# SCH_LedGridWallHatV4_2026-08-28.net
KiCad netlist of a schematic drawn in EasyEDA
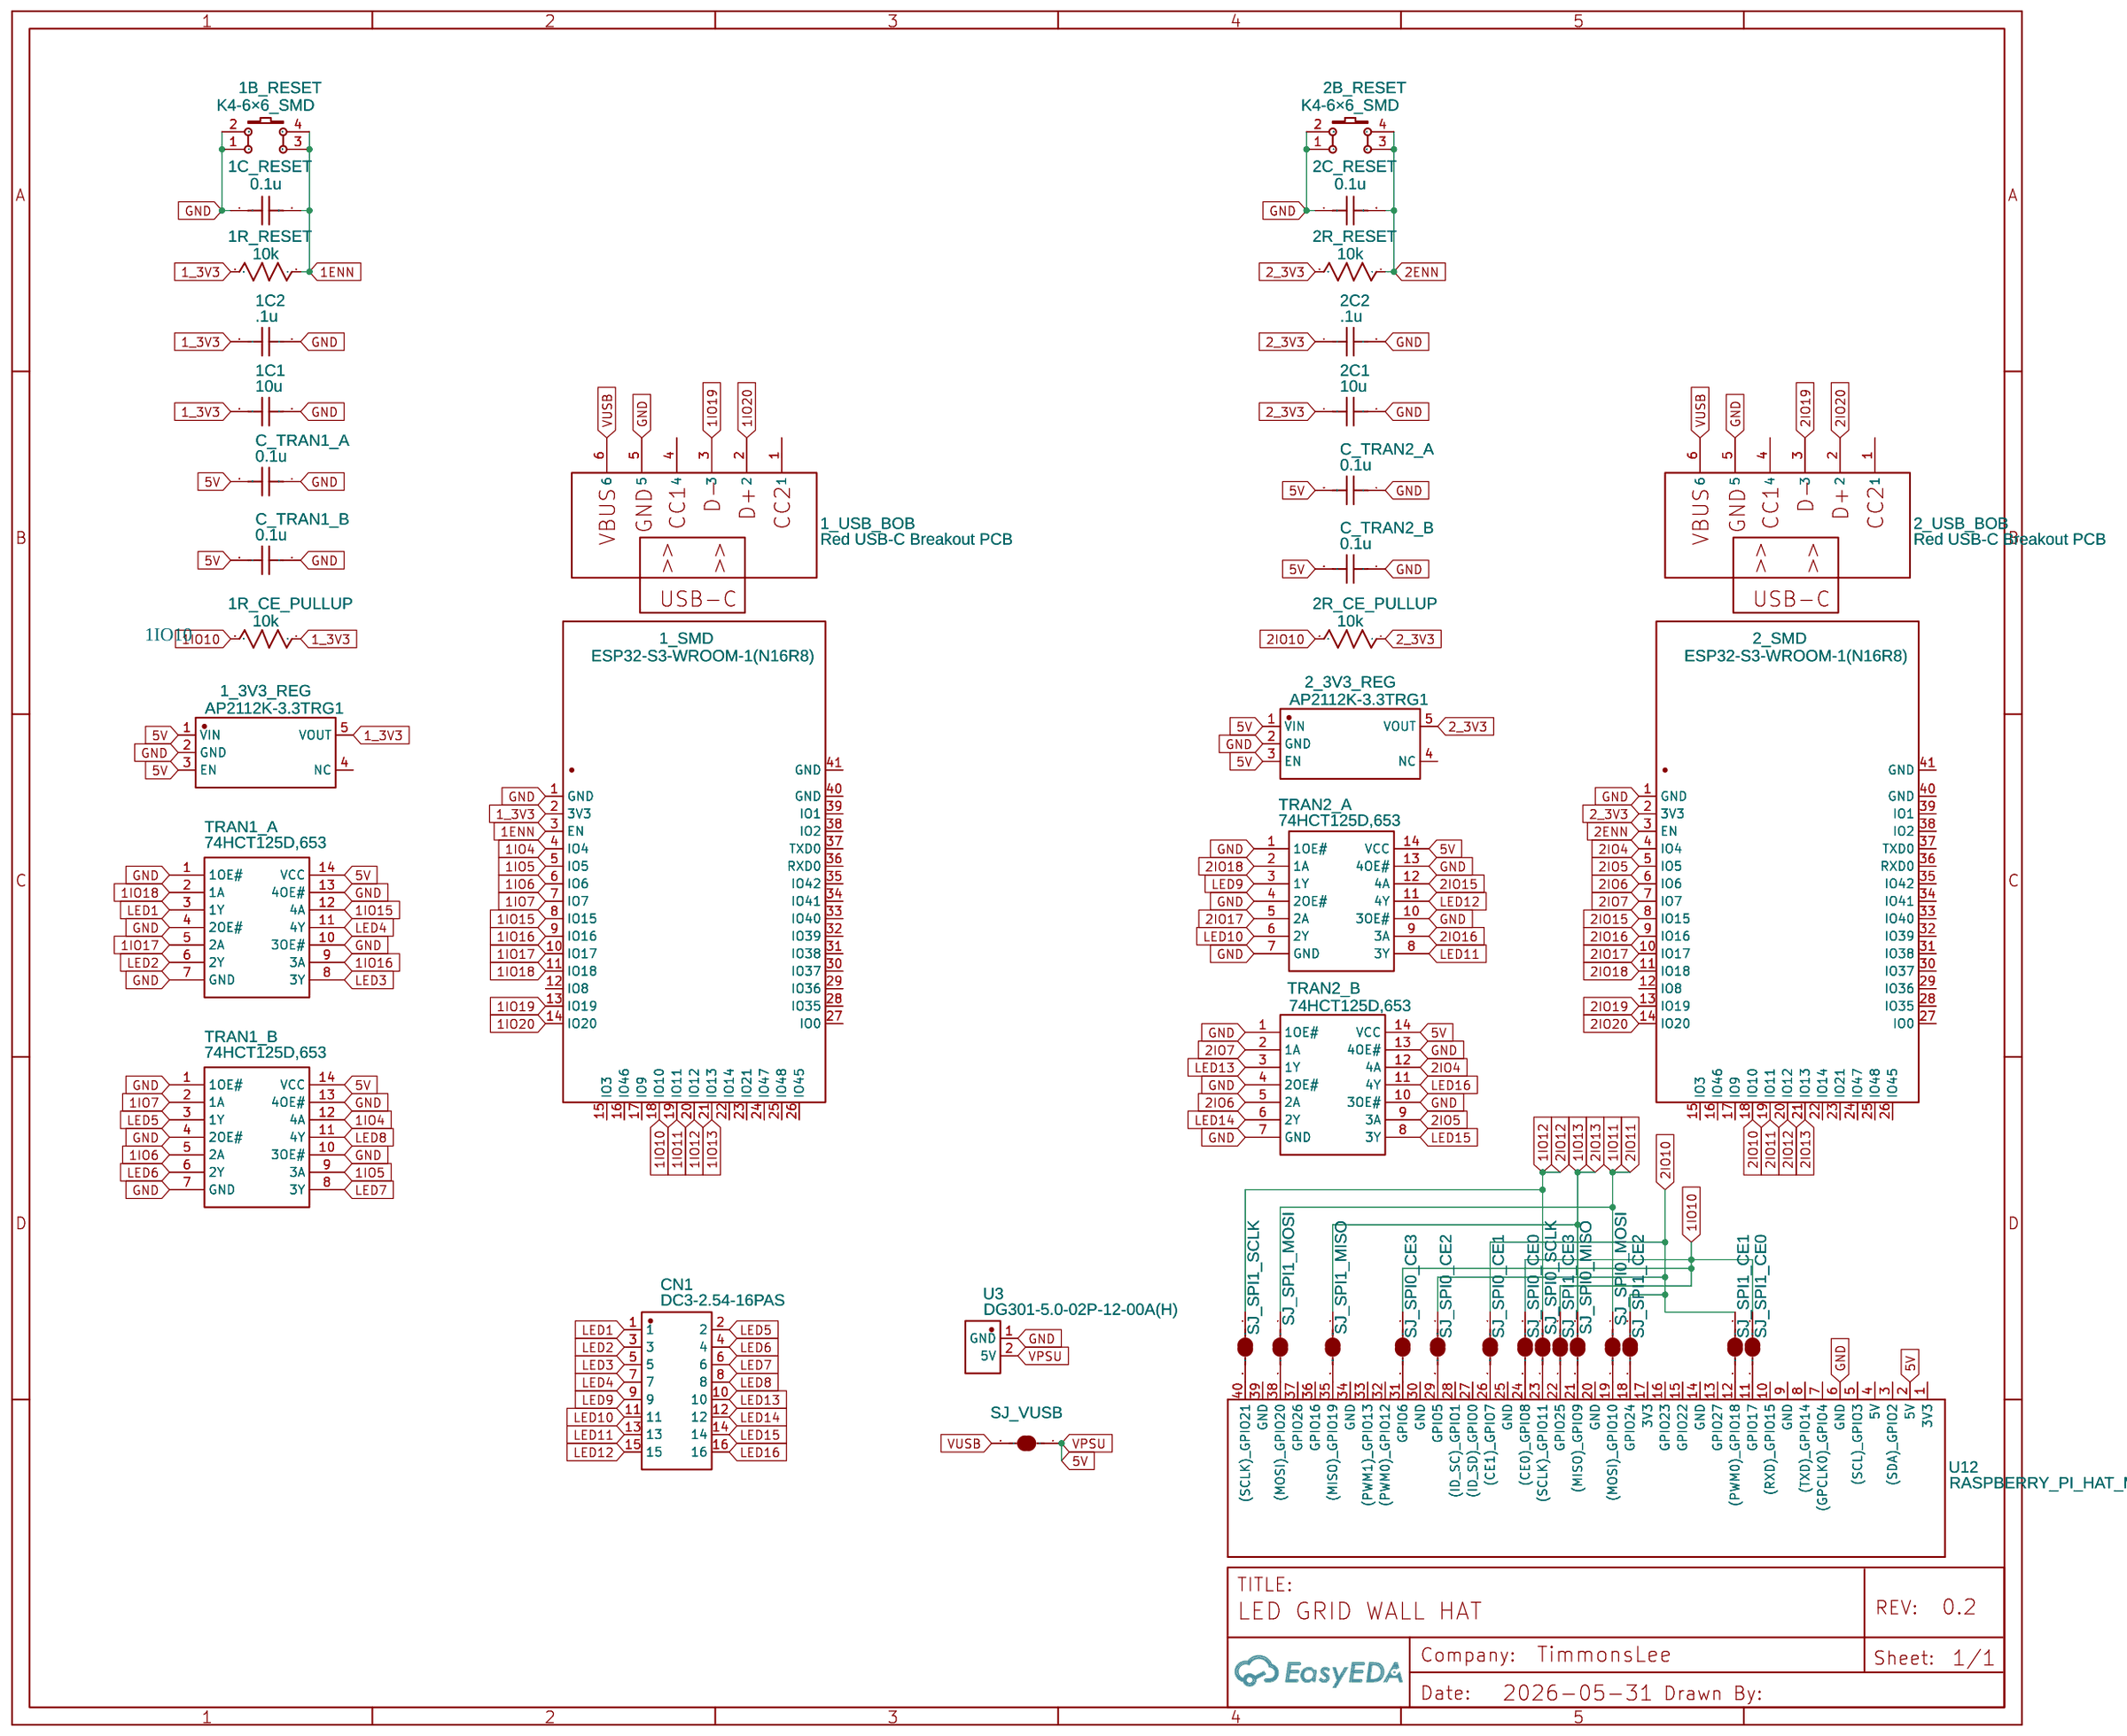
[diagram p0: schematic sheet]

(export (version "E")
  (design (tool "Eeschema 10.0.6"))
  (components
    (comp (ref "1B_RESET")
      (value "K4-6×6_SMD")
      (fields (field (name "Manufacturer Part") "K2-6639SP-D4SC-04") (field (name "Manufacturer") "韩国韩荣"))
      (libsource (lib "") (part "K4-6×6_SMD_1"))
    )
    (comp (ref "1C1") (value "10u") (libsource (lib "") (part "C_1206_US")))
    (comp (ref "1C2") (value ".1u") (libsource (lib "") (part "C_1206_US")))
    (comp (ref "1C_RESET") (value "0.1u") (libsource (lib "") (part "C_1206_US_3")))
    (comp (ref "1R_CE_PULLUP") (value "10k") (libsource (lib "") (part "R_1206_US_1")))
    (comp (ref "1R_RESET") (value "10k") (libsource (lib "") (part "R_1206_US_2")))
    (comp (ref "1_3V3_REG")
      (value "AP2112K-3.3TRG1")
      (fields (field (name "Manufacturer") "DIODES(美台)"))
      (libsource (lib "") (part "AP2112K-3.3TRG1_1"))
    )
    (comp (ref "1_SMD")
      (value "ESP32-S3-WROOM-1(N16R8)")
      (fields
        (field (name "Manufacturer Part") "ESP32-S3-WROOM-1-N16R8")
        (field (name "Manufacturer") "ESPRESSIF(乐鑫)")
      )
      (libsource (lib "") (part "ESP32-S3-WROOM-1(N16R8)_1"))
    )
    (comp (ref "1_USB_BOB")
      (value "Red USB-C Breakout PCB")
      (libsource (lib "") (part "Red USB-C Breakout PCB"))
    )
    (comp (ref "2B_RESET")
      (value "K4-6×6_SMD")
      (fields (field (name "Manufacturer Part") "K2-6639SP-D4SC-04") (field (name "Manufacturer") "韩国韩荣"))
      (libsource (lib "") (part "K4-6×6_SMD"))
    )
    (comp (ref "2C1") (value "10u") (libsource (lib "") (part "C_1206_US_6")))
    (comp (ref "2C2") (value ".1u") (libsource (lib "") (part "C_1206_US_6")))
    (comp (ref "2C_RESET") (value "0.1u") (libsource (lib "") (part "C_1206_US_1")))
    (comp (ref "2R_CE_PULLUP") (value "10k") (libsource (lib "") (part "R_1206_US_3")))
    (comp (ref "2R_RESET") (value "10k") (libsource (lib "") (part "R_1206_US")))
    (comp (ref "2_3V3_REG")
      (value "AP2112K-3.3TRG1")
      (fields (field (name "Manufacturer") "DIODES(美台)"))
      (libsource (lib "") (part "AP2112K-3.3TRG1"))
    )
    (comp (ref "2_SMD")
      (value "ESP32-S3-WROOM-1(N16R8)")
      (fields
        (field (name "Manufacturer Part") "ESP32-S3-WROOM-1-N16R8")
        (field (name "Manufacturer") "ESPRESSIF(乐鑫)")
      )
      (libsource (lib "") (part "ESP32-S3-WROOM-1(N16R8)"))
    )
    (comp (ref "2_USB_BOB")
      (value "Red USB-C Breakout PCB")
      (libsource (lib "") (part "Red USB-C Breakout PCB_1"))
    )
    (comp (ref "CN1")
      (value "DC3-2.54-16PAS")
      (fields (field (name "Manufacturer") "ZHOURI(洲日)"))
      (libsource (lib "") (part "DC3-2.54-16PAS"))
    )
    (comp (ref "C_TRAN1_A") (value "0.1u") (libsource (lib "") (part "C_1206_US_5")))
    (comp (ref "C_TRAN1_B") (value "0.1u") (libsource (lib "") (part "C_1206_US_7")))
    (comp (ref "C_TRAN2_A") (value "0.1u") (libsource (lib "") (part "C_1206_US_4")))
    (comp (ref "C_TRAN2_B") (value "0.1u") (libsource (lib "") (part "C_1206_US_2")))
    (comp (ref "SJ_SPI0_CE0") (value "SOLDERJUMPERNO") (libsource (lib "") (part "SOLDERJUMPERNO_1")))
    (comp (ref "SJ_SPI0_CE1") (value "SOLDERJUMPERNO") (libsource (lib "") (part "SOLDERJUMPERNO_1")))
    (comp (ref "SJ_SPI0_CE2") (value "SOLDERJUMPERNO") (libsource (lib "") (part "SOLDERJUMPERNO_1")))
    (comp (ref "SJ_SPI0_CE3") (value "SOLDERJUMPERNO") (libsource (lib "") (part "SOLDERJUMPERNO_1")))
    (comp (ref "SJ_SPI0_MISO") (value "SOLDERJUMPERNO") (libsource (lib "") (part "SOLDERJUMPERNO_7")))
    (comp (ref "SJ_SPI0_MOSI") (value "SOLDERJUMPERNO") (libsource (lib "") (part "SOLDERJUMPERNO_2")))
    (comp (ref "SJ_SPI0_SCLK") (value "SOLDERJUMPERNO") (libsource (lib "") (part "SOLDERJUMPERNO_6")))
    (comp (ref "SJ_SPI1_CE0") (value "SOLDERJUMPERNO") (libsource (lib "") (part "SOLDERJUMPERNO_3")))
    (comp (ref "SJ_SPI1_CE1") (value "SOLDERJUMPERNO") (libsource (lib "") (part "SOLDERJUMPERNO_3")))
    (comp (ref "SJ_SPI1_CE2") (value "SOLDERJUMPERNO") (libsource (lib "") (part "SOLDERJUMPERNO_3")))
    (comp (ref "SJ_SPI1_CE3") (value "SOLDERJUMPERNO") (libsource (lib "") (part "SOLDERJUMPERNO_3")))
    (comp (ref "SJ_SPI1_MISO") (value "SOLDERJUMPERNO") (libsource (lib "") (part "SOLDERJUMPERNO_4")))
    (comp (ref "SJ_SPI1_MOSI") (value "SOLDERJUMPERNO") (libsource (lib "") (part "SOLDERJUMPERNO_8")))
    (comp (ref "SJ_SPI1_SCLK") (value "SOLDERJUMPERNO") (libsource (lib "") (part "SOLDERJUMPERNO_5")))
    (comp (ref "SJ_VUSB") (value "SOLDERJUMPERNO") (libsource (lib "") (part "SOLDERJUMPERNO")))
    (comp (ref "TRAN1_A")
      (value "74HCT125D,653")
      (fields (field (name "Manufacturer") "Nexperia(安世)"))
      (libsource (lib "") (part "74HCT125D,653_2"))
    )
    (comp (ref "TRAN1_B")
      (value "74HCT125D,653")
      (fields (field (name "Manufacturer") "Nexperia(安世)"))
      (libsource (lib "") (part "74HCT125D,653"))
    )
    (comp (ref "TRAN2_A")
      (value "74HCT125D,653")
      (fields (field (name "Manufacturer") "Nexperia(安世)"))
      (libsource (lib "") (part "74HCT125D,653_1"))
    )
    (comp (ref "TRAN2_B")
      (value "74HCT125D,653")
      (fields (field (name "Manufacturer") "Nexperia(安世)"))
      (libsource (lib "") (part "74HCT125D,653_3"))
    )
    (comp (ref "U3")
      (value "DG301-5.0-02P-12-00A(H)")
      (fields (field (name "Manufacturer") "DEGSON(高正/高松)"))
      (libsource (lib "") (part "DG301-5.0-02P-12-00A(H)"))
    )
    (comp (ref "U12")
      (value "RASPBERRY_PI_HAT_MIRROR")
      (fields (field (name "Manufacturer Part") "RaspberryPi 3"))
      (libsource (lib "") (part "RASPBERRY_PI_HAT_MIRROR"))
    )
  )
  (nets
    (net (code "1") (name "1ENN") (class "Default")
      (node (ref "1B_RESET") (pin "3") (pinfunction "3_3") (pintype "unspecified"))
      (node (ref "1B_RESET") (pin "4") (pinfunction "4_4") (pintype "unspecified"))
      (node (ref "1C_RESET") (pin "2") (pinfunction "2_2") (pintype "unspecified"))
      (node (ref "1R_RESET") (pin "1") (pinfunction "1_1") (pintype "unspecified"))
      (node (ref "1_SMD") (pin "3") (pinfunction "EN_3") (pintype "unspecified"))
    )
    (net (code "2") (name "1IO4") (class "Default")
      (node (ref "1_SMD") (pin "4") (pinfunction "IO4_4") (pintype "unspecified"))
      (node (ref "TRAN1_B") (pin "12") (pinfunction "4A_12") (pintype "unspecified"))
    )
    (net (code "3") (name "1IO5") (class "Default")
      (node (ref "1_SMD") (pin "5") (pinfunction "IO5_5") (pintype "unspecified"))
      (node (ref "TRAN1_B") (pin "9") (pinfunction "3A_9") (pintype "unspecified"))
    )
    (net (code "4") (name "1IO6") (class "Default")
      (node (ref "1_SMD") (pin "6") (pinfunction "IO6_6") (pintype "unspecified"))
      (node (ref "TRAN1_B") (pin "5") (pinfunction "2A_5") (pintype "unspecified"))
    )
    (net (code "5") (name "1IO7") (class "Default")
      (node (ref "1_SMD") (pin "7") (pinfunction "IO7_7") (pintype "unspecified"))
      (node (ref "TRAN1_B") (pin "2") (pinfunction "1A_2") (pintype "unspecified"))
    )
    (net (code "6") (name "1IO10") (class "Default")
      (node (ref "1R_CE_PULLUP") (pin "2") (pinfunction "2_2") (pintype "unspecified"))
      (node (ref "1_SMD") (pin "18") (pinfunction "IO10_18") (pintype "unspecified"))
      (node (ref "SJ_SPI0_CE0") (pin "1") (pinfunction "1_1") (pintype "unspecified"))
      (node (ref "SJ_SPI0_CE3") (pin "1") (pinfunction "1_1") (pintype "unspecified"))
      (node (ref "SJ_SPI1_CE0") (pin "1") (pinfunction "1_1") (pintype "unspecified"))
      (node (ref "SJ_SPI1_CE3") (pin "1") (pinfunction "1_1") (pintype "unspecified"))
    )
    (net (code "7") (name "1IO11") (class "Default")
      (node (ref "1_SMD") (pin "19") (pinfunction "IO11_19") (pintype "unspecified"))
      (node (ref "2_SMD") (pin "19") (pinfunction "IO11_19") (pintype "unspecified"))
      (node (ref "SJ_SPI0_MOSI") (pin "1") (pinfunction "1_1") (pintype "unspecified"))
      (node (ref "SJ_SPI1_MOSI") (pin "1") (pinfunction "1_1") (pintype "unspecified"))
    )
    (net (code "8") (name "1IO12") (class "Default")
      (node (ref "1_SMD") (pin "20") (pinfunction "IO12_20") (pintype "unspecified"))
      (node (ref "2_SMD") (pin "20") (pinfunction "IO12_20") (pintype "unspecified"))
      (node (ref "SJ_SPI0_SCLK") (pin "1") (pinfunction "1_1") (pintype "unspecified"))
      (node (ref "SJ_SPI1_SCLK") (pin "1") (pinfunction "1_1") (pintype "unspecified"))
    )
    (net (code "9") (name "1IO13") (class "Default")
      (node (ref "1_SMD") (pin "21") (pinfunction "IO13_21") (pintype "unspecified"))
      (node (ref "2_SMD") (pin "21") (pinfunction "IO13_21") (pintype "unspecified"))
      (node (ref "SJ_SPI0_MISO") (pin "1") (pinfunction "1_1") (pintype "unspecified"))
      (node (ref "SJ_SPI1_MISO") (pin "1") (pinfunction "1_1") (pintype "unspecified"))
    )
    (net (code "10") (name "1IO15") (class "Default")
      (node (ref "1_SMD") (pin "8") (pinfunction "IO15_8") (pintype "unspecified"))
      (node (ref "TRAN1_A") (pin "12") (pinfunction "4A_12") (pintype "unspecified"))
    )
    (net (code "11") (name "1IO16") (class "Default")
      (node (ref "1_SMD") (pin "9") (pinfunction "IO16_9") (pintype "unspecified"))
      (node (ref "TRAN1_A") (pin "9") (pinfunction "3A_9") (pintype "unspecified"))
    )
    (net (code "12") (name "1IO17") (class "Default")
      (node (ref "1_SMD") (pin "10") (pinfunction "IO17_10") (pintype "unspecified"))
      (node (ref "TRAN1_A") (pin "5") (pinfunction "2A_5") (pintype "unspecified"))
    )
    (net (code "13") (name "1IO18") (class "Default")
      (node (ref "1_SMD") (pin "11") (pinfunction "IO18_11") (pintype "unspecified"))
      (node (ref "TRAN1_A") (pin "2") (pinfunction "1A_2") (pintype "unspecified"))
    )
    (net (code "14") (name "1IO19") (class "Default")
      (node (ref "1_SMD") (pin "13") (pinfunction "IO19_13") (pintype "unspecified"))
      (node (ref "1_USB_BOB") (pin "3") (pinfunction "3_3") (pintype "unspecified"))
    )
    (net (code "15") (name "1IO20") (class "Default")
      (node (ref "1_SMD") (pin "14") (pinfunction "IO20_14") (pintype "unspecified"))
      (node (ref "1_USB_BOB") (pin "2") (pinfunction "2_2") (pintype "unspecified"))
    )
    (net (code "16") (name "1_3V3") (class "Default")
      (node (ref "1C1") (pin "1") (pinfunction "1_1") (pintype "unspecified"))
      (node (ref "1C2") (pin "1") (pinfunction "1_1") (pintype "unspecified"))
      (node (ref "1R_CE_PULLUP") (pin "1") (pinfunction "1_1") (pintype "unspecified"))
      (node (ref "1R_RESET") (pin "2") (pinfunction "2_2") (pintype "unspecified"))
      (node (ref "1_3V3_REG") (pin "5") (pinfunction "VOUT_5") (pintype "unspecified"))
      (node (ref "1_SMD") (pin "2") (pinfunction "3V3_2") (pintype "unspecified"))
    )
    (net (code "17") (name "2ENN") (class "Default")
      (node (ref "2B_RESET") (pin "3") (pinfunction "3_3") (pintype "unspecified"))
      (node (ref "2B_RESET") (pin "4") (pinfunction "4_4") (pintype "unspecified"))
      (node (ref "2C_RESET") (pin "2") (pinfunction "2_2") (pintype "unspecified"))
      (node (ref "2R_RESET") (pin "1") (pinfunction "1_1") (pintype "unspecified"))
      (node (ref "2_SMD") (pin "3") (pinfunction "EN_3") (pintype "unspecified"))
    )
    (net (code "18") (name "2IO4") (class "Default")
      (node (ref "2_SMD") (pin "4") (pinfunction "IO4_4") (pintype "unspecified"))
      (node (ref "TRAN2_B") (pin "12") (pinfunction "4A_12") (pintype "unspecified"))
    )
    (net (code "19") (name "2IO5") (class "Default")
      (node (ref "2_SMD") (pin "5") (pinfunction "IO5_5") (pintype "unspecified"))
      (node (ref "TRAN2_B") (pin "9") (pinfunction "3A_9") (pintype "unspecified"))
    )
    (net (code "20") (name "2IO6") (class "Default")
      (node (ref "2_SMD") (pin "6") (pinfunction "IO6_6") (pintype "unspecified"))
      (node (ref "TRAN2_B") (pin "5") (pinfunction "2A_5") (pintype "unspecified"))
    )
    (net (code "21") (name "2IO7") (class "Default")
      (node (ref "2_SMD") (pin "7") (pinfunction "IO7_7") (pintype "unspecified"))
      (node (ref "TRAN2_B") (pin "2") (pinfunction "1A_2") (pintype "unspecified"))
    )
    (net (code "22") (name "2IO10") (class "Default")
      (node (ref "2R_CE_PULLUP") (pin "2") (pinfunction "2_2") (pintype "unspecified"))
      (node (ref "2_SMD") (pin "18") (pinfunction "IO10_18") (pintype "unspecified"))
      (node (ref "SJ_SPI0_CE1") (pin "1") (pinfunction "1_1") (pintype "unspecified"))
      (node (ref "SJ_SPI0_CE2") (pin "1") (pinfunction "1_1") (pintype "unspecified"))
      (node (ref "SJ_SPI1_CE1") (pin "1") (pinfunction "1_1") (pintype "unspecified"))
      (node (ref "SJ_SPI1_CE2") (pin "1") (pinfunction "1_1") (pintype "unspecified"))
    )
    (net (code "23") (name "2IO15") (class "Default")
      (node (ref "2_SMD") (pin "8") (pinfunction "IO15_8") (pintype "unspecified"))
      (node (ref "TRAN2_A") (pin "12") (pinfunction "4A_12") (pintype "unspecified"))
    )
    (net (code "24") (name "2IO16") (class "Default")
      (node (ref "2_SMD") (pin "9") (pinfunction "IO16_9") (pintype "unspecified"))
      (node (ref "TRAN2_A") (pin "9") (pinfunction "3A_9") (pintype "unspecified"))
    )
    (net (code "25") (name "2IO17") (class "Default")
      (node (ref "2_SMD") (pin "10") (pinfunction "IO17_10") (pintype "unspecified"))
      (node (ref "TRAN2_A") (pin "5") (pinfunction "2A_5") (pintype "unspecified"))
    )
    (net (code "26") (name "2IO18") (class "Default")
      (node (ref "2_SMD") (pin "11") (pinfunction "IO18_11") (pintype "unspecified"))
      (node (ref "TRAN2_A") (pin "2") (pinfunction "1A_2") (pintype "unspecified"))
    )
    (net (code "27") (name "2IO19") (class "Default")
      (node (ref "2_SMD") (pin "13") (pinfunction "IO19_13") (pintype "unspecified"))
      (node (ref "2_USB_BOB") (pin "3") (pinfunction "3_3") (pintype "unspecified"))
    )
    (net (code "28") (name "2IO20") (class "Default")
      (node (ref "2_SMD") (pin "14") (pinfunction "IO20_14") (pintype "unspecified"))
      (node (ref "2_USB_BOB") (pin "2") (pinfunction "2_2") (pintype "unspecified"))
    )
    (net (code "29") (name "2_3V3") (class "Default")
      (node (ref "2C1") (pin "1") (pinfunction "1_1") (pintype "unspecified"))
      (node (ref "2C2") (pin "1") (pinfunction "1_1") (pintype "unspecified"))
      (node (ref "2R_CE_PULLUP") (pin "1") (pinfunction "1_1") (pintype "unspecified"))
      (node (ref "2R_RESET") (pin "2") (pinfunction "2_2") (pintype "unspecified"))
      (node (ref "2_3V3_REG") (pin "5") (pinfunction "VOUT_5") (pintype "unspecified"))
      (node (ref "2_SMD") (pin "2") (pinfunction "3V3_2") (pintype "unspecified"))
    )
    (net (code "30") (name "5V") (class "Default")
      (node (ref "1_3V3_REG") (pin "1") (pinfunction "VIN_1") (pintype "unspecified"))
      (node (ref "1_3V3_REG") (pin "3") (pinfunction "EN_3") (pintype "unspecified"))
      (node (ref "2_3V3_REG") (pin "1") (pinfunction "VIN_1") (pintype "unspecified"))
      (node (ref "2_3V3_REG") (pin "3") (pinfunction "EN_3") (pintype "unspecified"))
      (node (ref "C_TRAN1_A") (pin "2") (pinfunction "2_2") (pintype "unspecified"))
      (node (ref "C_TRAN1_B") (pin "2") (pinfunction "2_2") (pintype "unspecified"))
      (node (ref "C_TRAN2_A") (pin "2") (pinfunction "2_2") (pintype "unspecified"))
      (node (ref "C_TRAN2_B") (pin "2") (pinfunction "2_2") (pintype "unspecified"))
      (node (ref "SJ_VUSB") (pin "1") (pinfunction "1_1") (pintype "unspecified"))
      (node (ref "TRAN1_A") (pin "14") (pinfunction "VCC_14") (pintype "unspecified"))
      (node (ref "TRAN1_B") (pin "14") (pinfunction "VCC_14") (pintype "unspecified"))
      (node (ref "TRAN2_A") (pin "14") (pinfunction "VCC_14") (pintype "unspecified"))
      (node (ref "TRAN2_B") (pin "14") (pinfunction "VCC_14") (pintype "unspecified"))
      (node (ref "U12") (pin "2") (pinfunction "5V_2") (pintype "unspecified"))
      (node (ref "U3") (pin "2") (pinfunction "5V_2") (pintype "unspecified"))
    )
    (net (code "31") (name "GND") (class "Default")
      (node (ref "1B_RESET") (pin "1") (pinfunction "1_1") (pintype "unspecified"))
      (node (ref "1B_RESET") (pin "2") (pinfunction "2_2") (pintype "unspecified"))
      (node (ref "1C1") (pin "2") (pinfunction "2_2") (pintype "unspecified"))
      (node (ref "1C2") (pin "2") (pinfunction "2_2") (pintype "unspecified"))
      (node (ref "1C_RESET") (pin "1") (pinfunction "1_1") (pintype "unspecified"))
      (node (ref "1_3V3_REG") (pin "2") (pinfunction "GND_2") (pintype "unspecified"))
      (node (ref "1_SMD") (pin "1") (pinfunction "GND_1") (pintype "unspecified"))
      (node (ref "1_USB_BOB") (pin "5") (pinfunction "5_5") (pintype "unspecified"))
      (node (ref "2B_RESET") (pin "1") (pinfunction "1_1") (pintype "unspecified"))
      (node (ref "2B_RESET") (pin "2") (pinfunction "2_2") (pintype "unspecified"))
      (node (ref "2C1") (pin "2") (pinfunction "2_2") (pintype "unspecified"))
      (node (ref "2C2") (pin "2") (pinfunction "2_2") (pintype "unspecified"))
      (node (ref "2C_RESET") (pin "1") (pinfunction "1_1") (pintype "unspecified"))
      (node (ref "2_3V3_REG") (pin "2") (pinfunction "GND_2") (pintype "unspecified"))
      (node (ref "2_SMD") (pin "1") (pinfunction "GND_1") (pintype "unspecified"))
      (node (ref "2_USB_BOB") (pin "5") (pinfunction "5_5") (pintype "unspecified"))
      (node (ref "C_TRAN1_A") (pin "1") (pinfunction "1_1") (pintype "unspecified"))
      (node (ref "C_TRAN1_B") (pin "1") (pinfunction "1_1") (pintype "unspecified"))
      (node (ref "C_TRAN2_A") (pin "1") (pinfunction "1_1") (pintype "unspecified"))
      (node (ref "C_TRAN2_B") (pin "1") (pinfunction "1_1") (pintype "unspecified"))
      (node (ref "TRAN1_A") (pin "1") (pinfunction "1OE#_1") (pintype "unspecified"))
      (node (ref "TRAN1_A") (pin "10") (pinfunction "3OE#_10") (pintype "unspecified"))
      (node (ref "TRAN1_A") (pin "13") (pinfunction "4OE#_13") (pintype "unspecified"))
      (node (ref "TRAN1_A") (pin "4") (pinfunction "2OE#_4") (pintype "unspecified"))
      (node (ref "TRAN1_A") (pin "7") (pinfunction "GND_7") (pintype "unspecified"))
      (node (ref "TRAN1_B") (pin "1") (pinfunction "1OE#_1") (pintype "unspecified"))
      (node (ref "TRAN1_B") (pin "10") (pinfunction "3OE#_10") (pintype "unspecified"))
      (node (ref "TRAN1_B") (pin "13") (pinfunction "4OE#_13") (pintype "unspecified"))
      (node (ref "TRAN1_B") (pin "4") (pinfunction "2OE#_4") (pintype "unspecified"))
      (node (ref "TRAN1_B") (pin "7") (pinfunction "GND_7") (pintype "unspecified"))
      (node (ref "TRAN2_A") (pin "1") (pinfunction "1OE#_1") (pintype "unspecified"))
      (node (ref "TRAN2_A") (pin "10") (pinfunction "3OE#_10") (pintype "unspecified"))
      (node (ref "TRAN2_A") (pin "13") (pinfunction "4OE#_13") (pintype "unspecified"))
      (node (ref "TRAN2_A") (pin "4") (pinfunction "2OE#_4") (pintype "unspecified"))
      (node (ref "TRAN2_A") (pin "7") (pinfunction "GND_7") (pintype "unspecified"))
      (node (ref "TRAN2_B") (pin "1") (pinfunction "1OE#_1") (pintype "unspecified"))
      (node (ref "TRAN2_B") (pin "10") (pinfunction "3OE#_10") (pintype "unspecified"))
      (node (ref "TRAN2_B") (pin "13") (pinfunction "4OE#_13") (pintype "unspecified"))
      (node (ref "TRAN2_B") (pin "4") (pinfunction "2OE#_4") (pintype "unspecified"))
      (node (ref "TRAN2_B") (pin "7") (pinfunction "GND_7") (pintype "unspecified"))
      (node (ref "U12") (pin "6") (pinfunction "GND_6") (pintype "unspecified"))
      (node (ref "U3") (pin "1") (pinfunction "GND_1") (pintype "unspecified"))
    )
    (net (code "32") (name "LED1") (class "Default")
      (node (ref "CN1") (pin "1") (pinfunction "1_1") (pintype "unspecified"))
      (node (ref "TRAN1_A") (pin "3") (pinfunction "1Y_3") (pintype "unspecified"))
    )
    (net (code "33") (name "LED2") (class "Default")
      (node (ref "CN1") (pin "3") (pinfunction "3_3") (pintype "unspecified"))
      (node (ref "TRAN1_A") (pin "6") (pinfunction "2Y_6") (pintype "unspecified"))
    )
    (net (code "34") (name "LED3") (class "Default")
      (node (ref "CN1") (pin "5") (pinfunction "5_5") (pintype "unspecified"))
      (node (ref "TRAN1_A") (pin "8") (pinfunction "3Y_8") (pintype "unspecified"))
    )
    (net (code "35") (name "LED4") (class "Default")
      (node (ref "CN1") (pin "7") (pinfunction "7_7") (pintype "unspecified"))
      (node (ref "TRAN1_A") (pin "11") (pinfunction "4Y_11") (pintype "unspecified"))
    )
    (net (code "36") (name "LED5") (class "Default")
      (node (ref "CN1") (pin "2") (pinfunction "2_2") (pintype "unspecified"))
      (node (ref "TRAN1_B") (pin "3") (pinfunction "1Y_3") (pintype "unspecified"))
    )
    (net (code "37") (name "LED6") (class "Default")
      (node (ref "CN1") (pin "4") (pinfunction "4_4") (pintype "unspecified"))
      (node (ref "TRAN1_B") (pin "6") (pinfunction "2Y_6") (pintype "unspecified"))
    )
    (net (code "38") (name "LED7") (class "Default")
      (node (ref "CN1") (pin "6") (pinfunction "6_6") (pintype "unspecified"))
      (node (ref "TRAN1_B") (pin "8") (pinfunction "3Y_8") (pintype "unspecified"))
    )
    (net (code "39") (name "LED8") (class "Default")
      (node (ref "CN1") (pin "8") (pinfunction "8_8") (pintype "unspecified"))
      (node (ref "TRAN1_B") (pin "11") (pinfunction "4Y_11") (pintype "unspecified"))
    )
    (net (code "40") (name "LED9") (class "Default")
      (node (ref "CN1") (pin "9") (pinfunction "9_9") (pintype "unspecified"))
      (node (ref "TRAN2_A") (pin "3") (pinfunction "1Y_3") (pintype "unspecified"))
    )
    (net (code "41") (name "LED10") (class "Default")
      (node (ref "CN1") (pin "11") (pinfunction "11_11") (pintype "unspecified"))
      (node (ref "TRAN2_A") (pin "6") (pinfunction "2Y_6") (pintype "unspecified"))
    )
    (net (code "42") (name "LED11") (class "Default")
      (node (ref "CN1") (pin "13") (pinfunction "13_13") (pintype "unspecified"))
      (node (ref "TRAN2_A") (pin "8") (pinfunction "3Y_8") (pintype "unspecified"))
    )
    (net (code "43") (name "LED12") (class "Default")
      (node (ref "CN1") (pin "15") (pinfunction "15_15") (pintype "unspecified"))
      (node (ref "TRAN2_A") (pin "11") (pinfunction "4Y_11") (pintype "unspecified"))
    )
    (net (code "44") (name "LED13") (class "Default")
      (node (ref "CN1") (pin "10") (pinfunction "10_10") (pintype "unspecified"))
      (node (ref "TRAN2_B") (pin "3") (pinfunction "1Y_3") (pintype "unspecified"))
    )
    (net (code "45") (name "LED14") (class "Default")
      (node (ref "CN1") (pin "12") (pinfunction "12_12") (pintype "unspecified"))
      (node (ref "TRAN2_B") (pin "6") (pinfunction "2Y_6") (pintype "unspecified"))
    )
    (net (code "46") (name "LED15") (class "Default")
      (node (ref "CN1") (pin "14") (pinfunction "14_14") (pintype "unspecified"))
      (node (ref "TRAN2_B") (pin "8") (pinfunction "3Y_8") (pintype "unspecified"))
    )
    (net (code "47") (name "LED16") (class "Default")
      (node (ref "CN1") (pin "16") (pinfunction "16_16") (pintype "unspecified"))
      (node (ref "TRAN2_B") (pin "11") (pinfunction "4Y_11") (pintype "unspecified"))
    )
    (net (code "48") (name "Net-(U12-(CE0)_GPIO8)") (class "Default")
      (node (ref "SJ_SPI0_CE0") (pin "2") (pinfunction "2_2") (pintype "unspecified"))
      (node (ref "U12") (pin "24") (pinfunction "(CE0)_GPIO8_24") (pintype "unspecified"))
    )
    (net (code "49") (name "Net-(U12-(CE1)_GPIO7)") (class "Default")
      (node (ref "SJ_SPI0_CE1") (pin "2") (pinfunction "2_2") (pintype "unspecified"))
      (node (ref "U12") (pin "26") (pinfunction "(CE1)_GPIO7_26") (pintype "unspecified"))
    )
    (net (code "50") (name "Net-(U12-(MISO)_GPIO9)") (class "Default")
      (node (ref "SJ_SPI0_MISO") (pin "2") (pinfunction "2_2") (pintype "unspecified"))
      (node (ref "U12") (pin "21") (pinfunction "(MISO)_GPIO9_21") (pintype "unspecified"))
    )
    (net (code "51") (name "Net-(U12-(MISO)_GPIO19)") (class "Default")
      (node (ref "SJ_SPI1_MISO") (pin "2") (pinfunction "2_2") (pintype "unspecified"))
      (node (ref "U12") (pin "35") (pinfunction "(MISO)_GPIO19_35") (pintype "unspecified"))
    )
    (net (code "52") (name "Net-(U12-(MOSI)_GPIO10)") (class "Default")
      (node (ref "SJ_SPI0_MOSI") (pin "2") (pinfunction "2_2") (pintype "unspecified"))
      (node (ref "U12") (pin "19") (pinfunction "(MOSI)_GPIO10_19") (pintype "unspecified"))
    )
    (net (code "53") (name "Net-(U12-(MOSI)_GPIO20)") (class "Default")
      (node (ref "SJ_SPI1_MOSI") (pin "2") (pinfunction "2_2") (pintype "unspecified"))
      (node (ref "U12") (pin "38") (pinfunction "(MOSI)_GPIO20_38") (pintype "unspecified"))
    )
    (net (code "54") (name "Net-(U12-(PWM0)_GPIO18)") (class "Default")
      (node (ref "SJ_SPI1_CE1") (pin "2") (pinfunction "2_2") (pintype "unspecified"))
      (node (ref "U12") (pin "12") (pinfunction "(PWM0)_GPIO18_12") (pintype "unspecified"))
    )
    (net (code "55") (name "Net-(U12-(SCLK)_GPIO11)") (class "Default")
      (node (ref "SJ_SPI0_SCLK") (pin "2") (pinfunction "2_2") (pintype "unspecified"))
      (node (ref "U12") (pin "23") (pinfunction "(SCLK)_GPIO11_23") (pintype "unspecified"))
    )
    (net (code "56") (name "Net-(U12-(SCLK)_GPIO21)") (class "Default")
      (node (ref "SJ_SPI1_SCLK") (pin "2") (pinfunction "2_2") (pintype "unspecified"))
      (node (ref "U12") (pin "40") (pinfunction "(SCLK)_GPIO21_40") (pintype "unspecified"))
    )
    (net (code "57") (name "Net-(U12-GPIO5)") (class "Default")
      (node (ref "SJ_SPI0_CE2") (pin "2") (pinfunction "2_2") (pintype "unspecified"))
      (node (ref "U12") (pin "29") (pinfunction "GPIO5_29") (pintype "unspecified"))
    )
    (net (code "58") (name "Net-(U12-GPIO6)") (class "Default")
      (node (ref "SJ_SPI0_CE3") (pin "2") (pinfunction "2_2") (pintype "unspecified"))
      (node (ref "U12") (pin "31") (pinfunction "GPIO6_31") (pintype "unspecified"))
    )
    (net (code "59") (name "Net-(U12-GPIO17)") (class "Default")
      (node (ref "SJ_SPI1_CE0") (pin "2") (pinfunction "2_2") (pintype "unspecified"))
      (node (ref "U12") (pin "11") (pinfunction "GPIO17_11") (pintype "unspecified"))
    )
    (net (code "60") (name "Net-(U12-GPIO24)") (class "Default")
      (node (ref "SJ_SPI1_CE2") (pin "2") (pinfunction "2_2") (pintype "unspecified"))
      (node (ref "U12") (pin "18") (pinfunction "GPIO24_18") (pintype "unspecified"))
    )
    (net (code "61") (name "Net-(U12-GPIO25)") (class "Default")
      (node (ref "SJ_SPI1_CE3") (pin "2") (pinfunction "2_2") (pintype "unspecified"))
      (node (ref "U12") (pin "22") (pinfunction "GPIO25_22") (pintype "unspecified"))
    )
    (net (code "62") (name "VUSB") (class "Default")
      (node (ref "1_USB_BOB") (pin "6") (pinfunction "6_6") (pintype "unspecified"))
      (node (ref "2_USB_BOB") (pin "6") (pinfunction "6_6") (pintype "unspecified"))
      (node (ref "SJ_VUSB") (pin "2") (pinfunction "2_2") (pintype "unspecified"))
    )
    (net (code "63") (name "unconnected-(1_3V3_REG-NC-Pad4)") (class "Default")
      (node (ref "1_3V3_REG") (pin "4") (pinfunction "NC_4") (pintype "unspecified"))
    )
    (net (code "64") (name "unconnected-(1_SMD-GND-Pad40)") (class "Default")
      (node (ref "1_SMD") (pin "40") (pinfunction "GND_40") (pintype "unspecified"))
    )
    (net (code "65") (name "unconnected-(1_SMD-GND-Pad41)") (class "Default")
      (node (ref "1_SMD") (pin "41") (pinfunction "GND_41") (pintype "unspecified"))
    )
    (net (code "66") (name "unconnected-(1_SMD-IO0-Pad27)") (class "Default")
      (node (ref "1_SMD") (pin "27") (pinfunction "IO0_27") (pintype "unspecified"))
    )
    (net (code "67") (name "unconnected-(1_SMD-IO1-Pad39)") (class "Default")
      (node (ref "1_SMD") (pin "39") (pinfunction "IO1_39") (pintype "unspecified"))
    )
    (net (code "68") (name "unconnected-(1_SMD-IO2-Pad38)") (class "Default")
      (node (ref "1_SMD") (pin "38") (pinfunction "IO2_38") (pintype "unspecified"))
    )
    (net (code "69") (name "unconnected-(1_SMD-IO3-Pad15)") (class "Default")
      (node (ref "1_SMD") (pin "15") (pinfunction "IO3_15") (pintype "unspecified"))
    )
    (net (code "70") (name "unconnected-(1_SMD-IO8-Pad12)") (class "Default")
      (node (ref "1_SMD") (pin "12") (pinfunction "IO8_12") (pintype "unspecified"))
    )
    (net (code "71") (name "unconnected-(1_SMD-IO9-Pad17)") (class "Default")
      (node (ref "1_SMD") (pin "17") (pinfunction "IO9_17") (pintype "unspecified"))
    )
    (net (code "72") (name "unconnected-(1_SMD-IO14-Pad22)") (class "Default")
      (node (ref "1_SMD") (pin "22") (pinfunction "IO14_22") (pintype "unspecified"))
    )
    (net (code "73") (name "unconnected-(1_SMD-IO21-Pad23)") (class "Default")
      (node (ref "1_SMD") (pin "23") (pinfunction "IO21_23") (pintype "unspecified"))
    )
    (net (code "74") (name "unconnected-(1_SMD-IO35-Pad28)") (class "Default")
      (node (ref "1_SMD") (pin "28") (pinfunction "IO35_28") (pintype "unspecified"))
    )
    (net (code "75") (name "unconnected-(1_SMD-IO36-Pad29)") (class "Default")
      (node (ref "1_SMD") (pin "29") (pinfunction "IO36_29") (pintype "unspecified"))
    )
    (net (code "76") (name "unconnected-(1_SMD-IO37-Pad30)") (class "Default")
      (node (ref "1_SMD") (pin "30") (pinfunction "IO37_30") (pintype "unspecified"))
    )
    (net (code "77") (name "unconnected-(1_SMD-IO38-Pad31)") (class "Default")
      (node (ref "1_SMD") (pin "31") (pinfunction "IO38_31") (pintype "unspecified"))
    )
    (net (code "78") (name "unconnected-(1_SMD-IO39-Pad32)") (class "Default")
      (node (ref "1_SMD") (pin "32") (pinfunction "IO39_32") (pintype "unspecified"))
    )
    (net (code "79") (name "unconnected-(1_SMD-IO40-Pad33)") (class "Default")
      (node (ref "1_SMD") (pin "33") (pinfunction "IO40_33") (pintype "unspecified"))
    )
    (net (code "80") (name "unconnected-(1_SMD-IO41-Pad34)") (class "Default")
      (node (ref "1_SMD") (pin "34") (pinfunction "IO41_34") (pintype "unspecified"))
    )
    (net (code "81") (name "unconnected-(1_SMD-IO42-Pad35)") (class "Default")
      (node (ref "1_SMD") (pin "35") (pinfunction "IO42_35") (pintype "unspecified"))
    )
    (net (code "82") (name "unconnected-(1_SMD-IO45-Pad26)") (class "Default")
      (node (ref "1_SMD") (pin "26") (pinfunction "IO45_26") (pintype "unspecified"))
    )
    (net (code "83") (name "unconnected-(1_SMD-IO46-Pad16)") (class "Default")
      (node (ref "1_SMD") (pin "16") (pinfunction "IO46_16") (pintype "unspecified"))
    )
    (net (code "84") (name "unconnected-(1_SMD-IO47-Pad24)") (class "Default")
      (node (ref "1_SMD") (pin "24") (pinfunction "IO47_24") (pintype "unspecified"))
    )
    (net (code "85") (name "unconnected-(1_SMD-IO48-Pad25)") (class "Default")
      (node (ref "1_SMD") (pin "25") (pinfunction "IO48_25") (pintype "unspecified"))
    )
    (net (code "86") (name "unconnected-(1_SMD-RXD0-Pad36)") (class "Default")
      (node (ref "1_SMD") (pin "36") (pinfunction "RXD0_36") (pintype "unspecified"))
    )
    (net (code "87") (name "unconnected-(1_SMD-TXD0-Pad37)") (class "Default")
      (node (ref "1_SMD") (pin "37") (pinfunction "TXD0_37") (pintype "unspecified"))
    )
    (net (code "88") (name "unconnected-(1_USB_BOB-Pad1)") (class "Default")
      (node (ref "1_USB_BOB") (pin "1") (pinfunction "1_1") (pintype "unspecified"))
    )
    (net (code "89") (name "unconnected-(1_USB_BOB-Pad4)") (class "Default")
      (node (ref "1_USB_BOB") (pin "4") (pinfunction "4_4") (pintype "unspecified"))
    )
    (net (code "90") (name "unconnected-(2_3V3_REG-NC-Pad4)") (class "Default")
      (node (ref "2_3V3_REG") (pin "4") (pinfunction "NC_4") (pintype "unspecified"))
    )
    (net (code "91") (name "unconnected-(2_SMD-GND-Pad40)") (class "Default")
      (node (ref "2_SMD") (pin "40") (pinfunction "GND_40") (pintype "unspecified"))
    )
    (net (code "92") (name "unconnected-(2_SMD-GND-Pad41)") (class "Default")
      (node (ref "2_SMD") (pin "41") (pinfunction "GND_41") (pintype "unspecified"))
    )
    (net (code "93") (name "unconnected-(2_SMD-IO0-Pad27)") (class "Default")
      (node (ref "2_SMD") (pin "27") (pinfunction "IO0_27") (pintype "unspecified"))
    )
    (net (code "94") (name "unconnected-(2_SMD-IO1-Pad39)") (class "Default")
      (node (ref "2_SMD") (pin "39") (pinfunction "IO1_39") (pintype "unspecified"))
    )
    (net (code "95") (name "unconnected-(2_SMD-IO2-Pad38)") (class "Default")
      (node (ref "2_SMD") (pin "38") (pinfunction "IO2_38") (pintype "unspecified"))
    )
    (net (code "96") (name "unconnected-(2_SMD-IO3-Pad15)") (class "Default")
      (node (ref "2_SMD") (pin "15") (pinfunction "IO3_15") (pintype "unspecified"))
    )
    (net (code "97") (name "unconnected-(2_SMD-IO8-Pad12)") (class "Default")
      (node (ref "2_SMD") (pin "12") (pinfunction "IO8_12") (pintype "unspecified"))
    )
    (net (code "98") (name "unconnected-(2_SMD-IO9-Pad17)") (class "Default")
      (node (ref "2_SMD") (pin "17") (pinfunction "IO9_17") (pintype "unspecified"))
    )
    (net (code "99") (name "unconnected-(2_SMD-IO14-Pad22)") (class "Default")
      (node (ref "2_SMD") (pin "22") (pinfunction "IO14_22") (pintype "unspecified"))
    )
    (net (code "100") (name "unconnected-(2_SMD-IO21-Pad23)") (class "Default")
      (node (ref "2_SMD") (pin "23") (pinfunction "IO21_23") (pintype "unspecified"))
    )
    (net (code "101") (name "unconnected-(2_SMD-IO35-Pad28)") (class "Default")
      (node (ref "2_SMD") (pin "28") (pinfunction "IO35_28") (pintype "unspecified"))
    )
    (net (code "102") (name "unconnected-(2_SMD-IO36-Pad29)") (class "Default")
      (node (ref "2_SMD") (pin "29") (pinfunction "IO36_29") (pintype "unspecified"))
    )
    (net (code "103") (name "unconnected-(2_SMD-IO37-Pad30)") (class "Default")
      (node (ref "2_SMD") (pin "30") (pinfunction "IO37_30") (pintype "unspecified"))
    )
    (net (code "104") (name "unconnected-(2_SMD-IO38-Pad31)") (class "Default")
      (node (ref "2_SMD") (pin "31") (pinfunction "IO38_31") (pintype "unspecified"))
    )
    (net (code "105") (name "unconnected-(2_SMD-IO39-Pad32)") (class "Default")
      (node (ref "2_SMD") (pin "32") (pinfunction "IO39_32") (pintype "unspecified"))
    )
    (net (code "106") (name "unconnected-(2_SMD-IO40-Pad33)") (class "Default")
      (node (ref "2_SMD") (pin "33") (pinfunction "IO40_33") (pintype "unspecified"))
    )
    (net (code "107") (name "unconnected-(2_SMD-IO41-Pad34)") (class "Default")
      (node (ref "2_SMD") (pin "34") (pinfunction "IO41_34") (pintype "unspecified"))
    )
    (net (code "108") (name "unconnected-(2_SMD-IO42-Pad35)") (class "Default")
      (node (ref "2_SMD") (pin "35") (pinfunction "IO42_35") (pintype "unspecified"))
    )
    (net (code "109") (name "unconnected-(2_SMD-IO45-Pad26)") (class "Default")
      (node (ref "2_SMD") (pin "26") (pinfunction "IO45_26") (pintype "unspecified"))
    )
    (net (code "110") (name "unconnected-(2_SMD-IO46-Pad16)") (class "Default")
      (node (ref "2_SMD") (pin "16") (pinfunction "IO46_16") (pintype "unspecified"))
    )
    (net (code "111") (name "unconnected-(2_SMD-IO47-Pad24)") (class "Default")
      (node (ref "2_SMD") (pin "24") (pinfunction "IO47_24") (pintype "unspecified"))
    )
    (net (code "112") (name "unconnected-(2_SMD-IO48-Pad25)") (class "Default")
      (node (ref "2_SMD") (pin "25") (pinfunction "IO48_25") (pintype "unspecified"))
    )
    (net (code "113") (name "unconnected-(2_SMD-RXD0-Pad36)") (class "Default")
      (node (ref "2_SMD") (pin "36") (pinfunction "RXD0_36") (pintype "unspecified"))
    )
    (net (code "114") (name "unconnected-(2_SMD-TXD0-Pad37)") (class "Default")
      (node (ref "2_SMD") (pin "37") (pinfunction "TXD0_37") (pintype "unspecified"))
    )
    (net (code "115") (name "unconnected-(2_USB_BOB-Pad1)") (class "Default")
      (node (ref "2_USB_BOB") (pin "1") (pinfunction "1_1") (pintype "unspecified"))
    )
    (net (code "116") (name "unconnected-(2_USB_BOB-Pad4)") (class "Default")
      (node (ref "2_USB_BOB") (pin "4") (pinfunction "4_4") (pintype "unspecified"))
    )
    (net (code "117") (name "unconnected-(U12-(GPCLK0)_GPIO4-Pad7)") (class "Default")
      (node (ref "U12") (pin "7") (pinfunction "(GPCLK0)_GPIO4_7") (pintype "unspecified"))
    )
    (net (code "118") (name "unconnected-(U12-(ID_SC)_GPIO1-Pad28)") (class "Default")
      (node (ref "U12") (pin "28") (pinfunction "(ID_SC)_GPIO1_28") (pintype "unspecified"))
    )
    (net (code "119") (name "unconnected-(U12-(ID_SD)_GPIO0-Pad27)") (class "Default")
      (node (ref "U12") (pin "27") (pinfunction "(ID_SD)_GPIO0_27") (pintype "unspecified"))
    )
    (net (code "120") (name "unconnected-(U12-(PWM0)_GPIO12-Pad32)") (class "Default")
      (node (ref "U12") (pin "32") (pinfunction "(PWM0)_GPIO12_32") (pintype "unspecified"))
    )
    (net (code "121") (name "unconnected-(U12-(PWM1)_GPIO13-Pad33)") (class "Default")
      (node (ref "U12") (pin "33") (pinfunction "(PWM1)_GPIO13_33") (pintype "unspecified"))
    )
    (net (code "122") (name "unconnected-(U12-(RXD)_GPIO15-Pad10)") (class "Default")
      (node (ref "U12") (pin "10") (pinfunction "(RXD)_GPIO15_10") (pintype "unspecified"))
    )
    (net (code "123") (name "unconnected-(U12-(SCL)_GPIO3-Pad5)") (class "Default")
      (node (ref "U12") (pin "5") (pinfunction "(SCL)_GPIO3_5") (pintype "unspecified"))
    )
    (net (code "124") (name "unconnected-(U12-(SDA)_GPIO2-Pad3)") (class "Default")
      (node (ref "U12") (pin "3") (pinfunction "(SDA)_GPIO2_3") (pintype "unspecified"))
    )
    (net (code "125") (name "unconnected-(U12-(TXD)_GPIO14-Pad8)") (class "Default")
      (node (ref "U12") (pin "8") (pinfunction "(TXD)_GPIO14_8") (pintype "unspecified"))
    )
    (net (code "126") (name "unconnected-(U12-3V3-Pad1)") (class "Default")
      (node (ref "U12") (pin "1") (pinfunction "3V3_1") (pintype "unspecified"))
    )
    (net (code "127") (name "unconnected-(U12-3V3-Pad17)") (class "Default")
      (node (ref "U12") (pin "17") (pinfunction "3V3_17") (pintype "unspecified"))
    )
    (net (code "128") (name "unconnected-(U12-5V-Pad4)") (class "Default")
      (node (ref "U12") (pin "4") (pinfunction "5V_4") (pintype "unspecified"))
    )
    (net (code "129") (name "unconnected-(U12-GND-Pad9)") (class "Default")
      (node (ref "U12") (pin "9") (pinfunction "GND_9") (pintype "unspecified"))
    )
    (net (code "130") (name "unconnected-(U12-GND-Pad14)") (class "Default")
      (node (ref "U12") (pin "14") (pinfunction "GND_14") (pintype "unspecified"))
    )
    (net (code "131") (name "unconnected-(U12-GND-Pad20)") (class "Default")
      (node (ref "U12") (pin "20") (pinfunction "GND_20") (pintype "unspecified"))
    )
    (net (code "132") (name "unconnected-(U12-GND-Pad25)") (class "Default")
      (node (ref "U12") (pin "25") (pinfunction "GND_25") (pintype "unspecified"))
    )
    (net (code "133") (name "unconnected-(U12-GND-Pad30)") (class "Default")
      (node (ref "U12") (pin "30") (pinfunction "GND_30") (pintype "unspecified"))
    )
    (net (code "134") (name "unconnected-(U12-GND-Pad34)") (class "Default")
      (node (ref "U12") (pin "34") (pinfunction "GND_34") (pintype "unspecified"))
    )
    (net (code "135") (name "unconnected-(U12-GND-Pad39)") (class "Default")
      (node (ref "U12") (pin "39") (pinfunction "GND_39") (pintype "unspecified"))
    )
    (net (code "136") (name "unconnected-(U12-GPIO16-Pad36)") (class "Default")
      (node (ref "U12") (pin "36") (pinfunction "GPIO16_36") (pintype "unspecified"))
    )
    (net (code "137") (name "unconnected-(U12-GPIO22-Pad15)") (class "Default")
      (node (ref "U12") (pin "15") (pinfunction "GPIO22_15") (pintype "unspecified"))
    )
    (net (code "138") (name "unconnected-(U12-GPIO23-Pad16)") (class "Default")
      (node (ref "U12") (pin "16") (pinfunction "GPIO23_16") (pintype "unspecified"))
    )
    (net (code "139") (name "unconnected-(U12-GPIO26-Pad37)") (class "Default")
      (node (ref "U12") (pin "37") (pinfunction "GPIO26_37") (pintype "unspecified"))
    )
    (net (code "140") (name "unconnected-(U12-GPIO27-Pad13)") (class "Default")
      (node (ref "U12") (pin "13") (pinfunction "GPIO27_13") (pintype "unspecified"))
    )
  )
)
